# main_9.net
KiCad netlist of a schematic drawn in Altium Designer
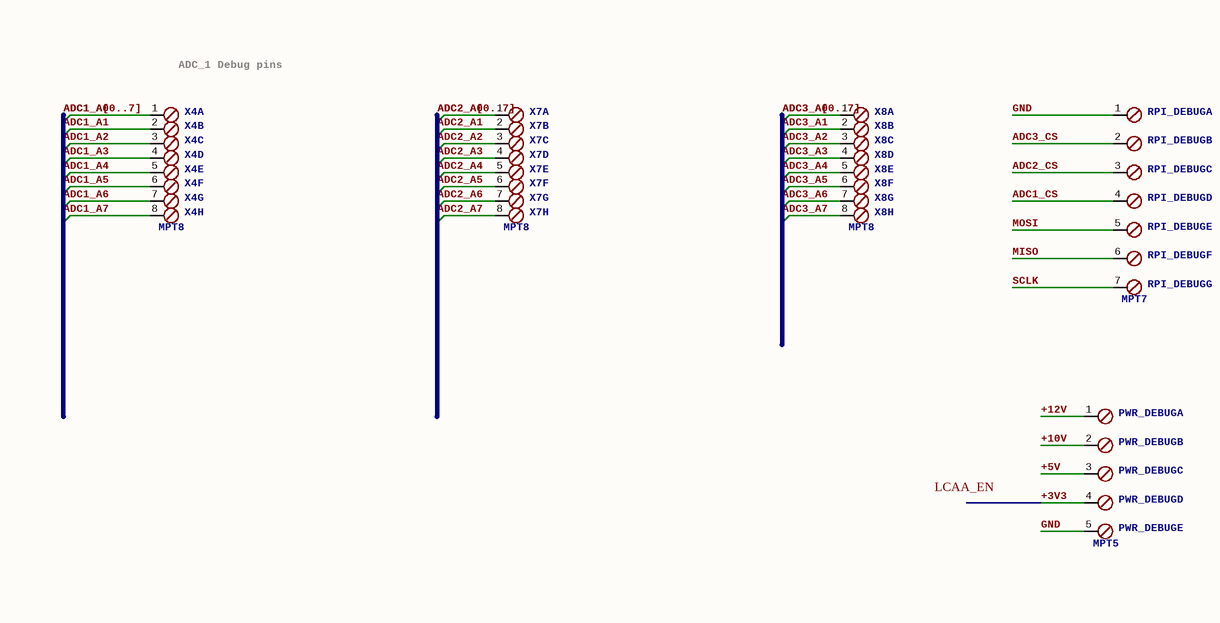
[diagram p0: main_9.SchDoc]

(export (version "E")
  (design (tool "Eeschema 10.0.6"))
  (components
    (comp (ref "PWR_DEBUG")
      (value "MPT5")
      (footprint "5POL254")
      (description "PHOENIX CONNECTOR")
      (libsource (lib "con-phoenix-254") (part "MPT5"))
    )
    (comp (ref "RPI_DEBUG")
      (value "MPT7")
      (footprint "7POL254")
      (description "PHOENIX CONNECTOR")
      (libsource (lib "con-phoenix-254") (part "MPT7"))
    )
    (comp (ref "X4")
      (value "MPT8")
      (footprint "8POL254")
      (description "PHOENIX CONNECTOR")
      (libsource (lib "con-phoenix-254") (part "MPT8"))
    )
    (comp (ref "X7")
      (value "MPT8")
      (footprint "8POL254")
      (description "PHOENIX CONNECTOR")
      (libsource (lib "con-phoenix-254") (part "MPT8"))
    )
    (comp (ref "X8")
      (value "MPT8")
      (footprint "8POL254")
      (description "PHOENIX CONNECTOR")
      (libsource (lib "con-phoenix-254") (part "MPT8"))
    )
  )
  (nets
    (net (code "25") (name "/+3V3") (class "Default")
      (node (ref "PWR_DEBUG") (pin "4") (pinfunction "1_4") (pintype "passive"))
    )
    (net (code "26") (name "/+5V") (class "Default")
      (node (ref "PWR_DEBUG") (pin "3") (pinfunction "1_3") (pintype "passive"))
    )
    (net (code "27") (name "/+10V") (class "Default")
      (node (ref "PWR_DEBUG") (pin "2") (pinfunction "1_2") (pintype "passive"))
    )
    (net (code "28") (name "/+12V") (class "Default")
      (node (ref "PWR_DEBUG") (pin "1") (pinfunction "1_1") (pintype "passive"))
    )
    (net (code "30") (name "/ADC1_CS") (class "Default")
      (node (ref "RPI_DEBUG") (pin "4") (pinfunction "1_4") (pintype "passive"))
    )
    (net (code "32") (name "/ADC2_CS") (class "Default")
      (node (ref "RPI_DEBUG") (pin "3") (pinfunction "1_3") (pintype "passive"))
    )
    (net (code "34") (name "/ADC3_CS") (class "Default")
      (node (ref "RPI_DEBUG") (pin "2") (pinfunction "1_2") (pintype "passive"))
    )
    (net (code "35") (name "/GND") (class "Default")
      (node (ref "PWR_DEBUG") (pin "5") (pinfunction "1_5") (pintype "passive"))
      (node (ref "RPI_DEBUG") (pin "1") (pinfunction "1_1") (pintype "passive"))
    )
    (net (code "37") (name "/MISO") (class "Default")
      (node (ref "RPI_DEBUG") (pin "6") (pinfunction "1_6") (pintype "passive"))
    )
    (net (code "38") (name "/MOSI") (class "Default")
      (node (ref "RPI_DEBUG") (pin "5") (pinfunction "1_5") (pintype "passive"))
    )
    (net (code "39") (name "/SCLK") (class "Default")
      (node (ref "RPI_DEBUG") (pin "7") (pinfunction "1_7") (pintype "passive"))
    )
    (net (code "40") (name "unconnected-(X4-Pad1)") (class "Default")
      (node (ref "X4") (pin "1") (pinfunction "1_1") (pintype "passive"))
    )
    (net (code "41") (name "unconnected-(X4B-1-Pad2)") (class "Default")
      (node (ref "X4") (pin "2") (pinfunction "1_2") (pintype "passive"))
    )
    (net (code "42") (name "unconnected-(X4C-1-Pad3)") (class "Default")
      (node (ref "X4") (pin "3") (pinfunction "1_3") (pintype "passive"))
    )
    (net (code "43") (name "unconnected-(X4D-1-Pad4)") (class "Default")
      (node (ref "X4") (pin "4") (pinfunction "1_4") (pintype "passive"))
    )
    (net (code "44") (name "unconnected-(X4E-1-Pad5)") (class "Default")
      (node (ref "X4") (pin "5") (pinfunction "1_5") (pintype "passive"))
    )
    (net (code "45") (name "unconnected-(X4F-1-Pad6)") (class "Default")
      (node (ref "X4") (pin "6") (pinfunction "1_6") (pintype "passive"))
    )
    (net (code "46") (name "unconnected-(X4G-1-Pad7)") (class "Default")
      (node (ref "X4") (pin "7") (pinfunction "1_7") (pintype "passive"))
    )
    (net (code "47") (name "unconnected-(X4H-1-Pad8)") (class "Default")
      (node (ref "X4") (pin "8") (pinfunction "1_8") (pintype "passive"))
    )
    (net (code "48") (name "unconnected-(X7-Pad1)") (class "Default")
      (node (ref "X7") (pin "1") (pinfunction "1_1") (pintype "passive"))
    )
    (net (code "49") (name "unconnected-(X7B-1-Pad2)") (class "Default")
      (node (ref "X7") (pin "2") (pinfunction "1_2") (pintype "passive"))
    )
    (net (code "50") (name "unconnected-(X7C-1-Pad3)") (class "Default")
      (node (ref "X7") (pin "3") (pinfunction "1_3") (pintype "passive"))
    )
    (net (code "51") (name "unconnected-(X7D-1-Pad4)") (class "Default")
      (node (ref "X7") (pin "4") (pinfunction "1_4") (pintype "passive"))
    )
    (net (code "52") (name "unconnected-(X7E-1-Pad5)") (class "Default")
      (node (ref "X7") (pin "5") (pinfunction "1_5") (pintype "passive"))
    )
    (net (code "53") (name "unconnected-(X7F-1-Pad6)") (class "Default")
      (node (ref "X7") (pin "6") (pinfunction "1_6") (pintype "passive"))
    )
    (net (code "54") (name "unconnected-(X7G-1-Pad7)") (class "Default")
      (node (ref "X7") (pin "7") (pinfunction "1_7") (pintype "passive"))
    )
    (net (code "55") (name "unconnected-(X7H-1-Pad8)") (class "Default")
      (node (ref "X7") (pin "8") (pinfunction "1_8") (pintype "passive"))
    )
    (net (code "56") (name "unconnected-(X8-Pad1)") (class "Default")
      (node (ref "X8") (pin "1") (pinfunction "1_1") (pintype "passive"))
    )
    (net (code "57") (name "unconnected-(X8B-1-Pad2)") (class "Default")
      (node (ref "X8") (pin "2") (pinfunction "1_2") (pintype "passive"))
    )
    (net (code "58") (name "unconnected-(X8C-1-Pad3)") (class "Default")
      (node (ref "X8") (pin "3") (pinfunction "1_3") (pintype "passive"))
    )
    (net (code "59") (name "unconnected-(X8D-1-Pad4)") (class "Default")
      (node (ref "X8") (pin "4") (pinfunction "1_4") (pintype "passive"))
    )
    (net (code "60") (name "unconnected-(X8E-1-Pad5)") (class "Default")
      (node (ref "X8") (pin "5") (pinfunction "1_5") (pintype "passive"))
    )
    (net (code "61") (name "unconnected-(X8F-1-Pad6)") (class "Default")
      (node (ref "X8") (pin "6") (pinfunction "1_6") (pintype "passive"))
    )
    (net (code "62") (name "unconnected-(X8G-1-Pad7)") (class "Default")
      (node (ref "X8") (pin "7") (pinfunction "1_7") (pintype "passive"))
    )
    (net (code "63") (name "unconnected-(X8H-1-Pad8)") (class "Default")
      (node (ref "X8") (pin "8") (pinfunction "1_8") (pintype "passive"))
    )
  )
)
